# 002_motordriver_mosfet.net
KiCad netlist of a schematic drawn in EAGLE
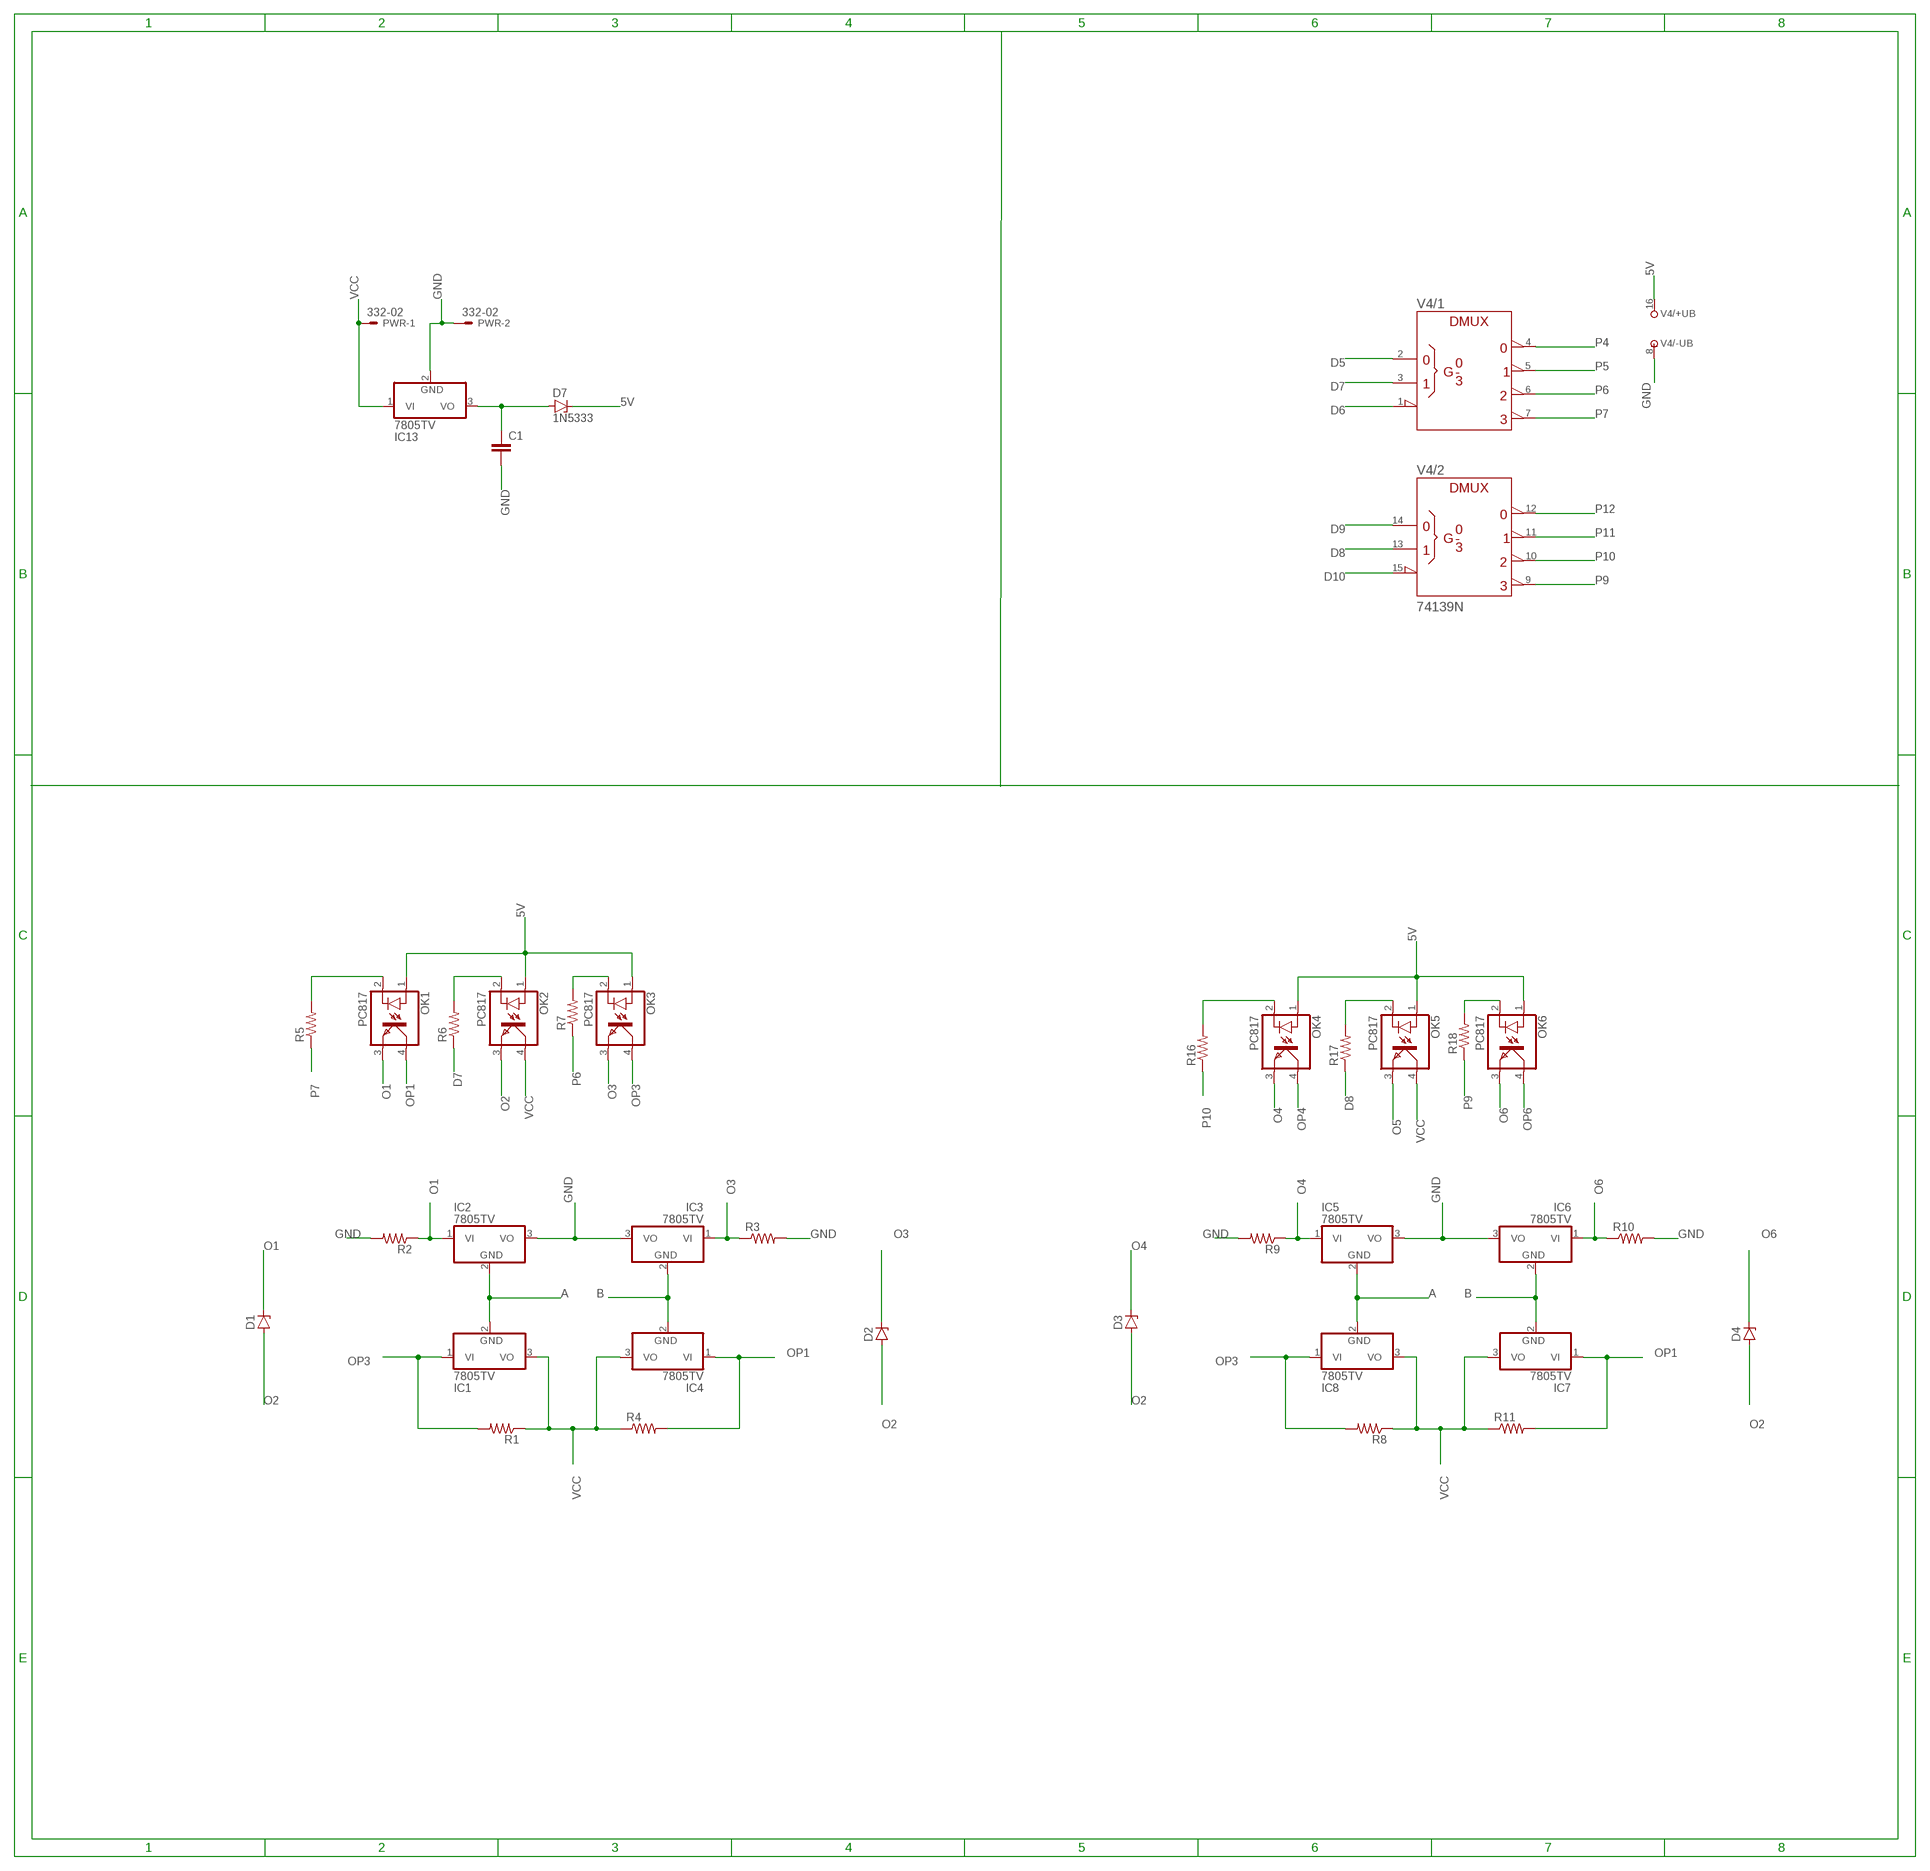
[diagram p0: schematic, sheet 1]

(export (version "E")
  (design (tool "Eeschema 10.0.6"))
  (components
    (comp (ref "C1")
      (value "C2,5-3")
      (footprint "eagle-import:C2.5-3")
      (libsource (lib "eagle-import") (part "C2,5-3"))
    )
    (comp (ref "D1")
      (value "ZENER-DIODEDO41Z10")
      (footprint "eagle-import:DO41Z10")
      (libsource (lib "eagle-import") (part "ZENER-DIODEDO41Z10"))
    )
    (comp (ref "D2")
      (value "ZENER-DIODEDO41Z10")
      (footprint "eagle-import:DO41Z10")
      (libsource (lib "eagle-import") (part "ZENER-DIODEDO41Z10"))
    )
    (comp (ref "D3")
      (value "ZENER-DIODEDO41Z10")
      (footprint "eagle-import:DO41Z10")
      (libsource (lib "eagle-import") (part "ZENER-DIODEDO41Z10"))
    )
    (comp (ref "D4")
      (value "ZENER-DIODEDO41Z10")
      (footprint "eagle-import:DO41Z10")
      (libsource (lib "eagle-import") (part "ZENER-DIODEDO41Z10"))
    )
    (comp (ref "D7")
      (value "1N5333")
      (footprint "eagle-import:C1702-15")
      (libsource (lib "eagle-import") (part "1N5333"))
    )
    (comp (ref "IC1")
      (value "7805TV")
      (footprint "eagle-import:TO220V")
      (libsource (lib "eagle-import") (part "78TV05"))
    )
    (comp (ref "IC2")
      (value "7805TV")
      (footprint "eagle-import:TO220V")
      (libsource (lib "eagle-import") (part "78TV05"))
    )
    (comp (ref "IC3")
      (value "7805TV")
      (footprint "eagle-import:TO220V")
      (libsource (lib "eagle-import") (part "78TV05"))
    )
    (comp (ref "IC4")
      (value "7805TV")
      (footprint "eagle-import:TO220V")
      (libsource (lib "eagle-import") (part "78TV05"))
    )
    (comp (ref "IC5")
      (value "7805TV")
      (footprint "eagle-import:TO220V")
      (libsource (lib "eagle-import") (part "78TV05"))
    )
    (comp (ref "IC6")
      (value "7805TV")
      (footprint "eagle-import:TO220V")
      (libsource (lib "eagle-import") (part "78TV05"))
    )
    (comp (ref "IC7")
      (value "7805TV")
      (footprint "eagle-import:TO220V")
      (libsource (lib "eagle-import") (part "78TV05"))
    )
    (comp (ref "IC8")
      (value "7805TV")
      (footprint "eagle-import:TO220V")
      (libsource (lib "eagle-import") (part "78TV05"))
    )
    (comp (ref "IC13")
      (value "7805TV")
      (footprint "eagle-import:TO220V")
      (libsource (lib "eagle-import") (part "78TV05"))
    )
    (comp (ref "OK1")
      (value "PC817")
      (footprint "eagle-import:DIL04")
      (fields (field (name "MPN") "PC817X4J000F"))
      (libsource (lib "eagle-import") (part "PC817"))
    )
    (comp (ref "OK2")
      (value "PC817")
      (footprint "eagle-import:DIL04")
      (fields (field (name "MPN") "PC817X4J000F"))
      (libsource (lib "eagle-import") (part "PC817"))
    )
    (comp (ref "OK3")
      (value "PC817")
      (footprint "eagle-import:DIL04")
      (fields (field (name "MPN") "PC817X4J000F"))
      (libsource (lib "eagle-import") (part "PC817"))
    )
    (comp (ref "OK4")
      (value "PC817")
      (footprint "eagle-import:DIL04")
      (fields (field (name "MPN") "PC817X4J000F"))
      (libsource (lib "eagle-import") (part "PC817"))
    )
    (comp (ref "OK5")
      (value "PC817")
      (footprint "eagle-import:DIL04")
      (fields (field (name "MPN") "PC817X4J000F"))
      (libsource (lib "eagle-import") (part "PC817"))
    )
    (comp (ref "OK6")
      (value "PC817")
      (footprint "eagle-import:DIL04")
      (fields (field (name "MPN") "PC817X4J000F"))
      (libsource (lib "eagle-import") (part "PC817"))
    )
    (comp (ref "PWR")
      (value "332-02")
      (footprint "eagle-import:332-02")
      (libsource (lib "eagle-import") (part "332-02"))
    )
    (comp (ref "R1")
      (value "R-US_M0805")
      (footprint "eagle-import:M0805")
      (libsource (lib "eagle-import") (part "R-US_M0805"))
    )
    (comp (ref "R2")
      (value "R-US_M0805")
      (footprint "eagle-import:M0805")
      (libsource (lib "eagle-import") (part "R-US_M0805"))
    )
    (comp (ref "R3")
      (value "R-US_M0805")
      (footprint "eagle-import:M0805")
      (libsource (lib "eagle-import") (part "R-US_M0805"))
    )
    (comp (ref "R4")
      (value "R-US_M0805")
      (footprint "eagle-import:M0805")
      (libsource (lib "eagle-import") (part "R-US_M0805"))
    )
    (comp (ref "R5")
      (value "R-US_M0805")
      (footprint "eagle-import:M0805")
      (libsource (lib "eagle-import") (part "R-US_M0805"))
    )
    (comp (ref "R6")
      (value "R-US_M0805")
      (footprint "eagle-import:M0805")
      (libsource (lib "eagle-import") (part "R-US_M0805"))
    )
    (comp (ref "R7")
      (value "R-US_M0805")
      (footprint "eagle-import:M0805")
      (libsource (lib "eagle-import") (part "R-US_M0805"))
    )
    (comp (ref "R8")
      (value "R-US_M0805")
      (footprint "eagle-import:M0805")
      (libsource (lib "eagle-import") (part "R-US_M0805"))
    )
    (comp (ref "R9")
      (value "R-US_M0805")
      (footprint "eagle-import:M0805")
      (libsource (lib "eagle-import") (part "R-US_M0805"))
    )
    (comp (ref "R10")
      (value "R-US_M0805")
      (footprint "eagle-import:M0805")
      (libsource (lib "eagle-import") (part "R-US_M0805"))
    )
    (comp (ref "R11")
      (value "R-US_M0805")
      (footprint "eagle-import:M0805")
      (libsource (lib "eagle-import") (part "R-US_M0805"))
    )
    (comp (ref "R16")
      (value "R-US_M0805")
      (footprint "eagle-import:M0805")
      (libsource (lib "eagle-import") (part "R-US_M0805"))
    )
    (comp (ref "R17")
      (value "R-US_M0805")
      (footprint "eagle-import:M0805")
      (libsource (lib "eagle-import") (part "R-US_M0805"))
    )
    (comp (ref "R18")
      (value "R-US_M0805")
      (footprint "eagle-import:M0805")
      (libsource (lib "eagle-import") (part "R-US_M0805"))
    )
    (comp (ref "V4")
      (value "74139N")
      (footprint "eagle-import:DIL16")
      (libsource (lib "eagle-import") (part "74139N"))
    )
  )
  (nets
    (net (code "1") (name "/5V") (class "Default")
      (node (ref "D7") (pin "C") (pinfunction "C_C") (pintype "passive"))
      (node (ref "OK1") (pin "1") (pinfunction "A_1") (pintype "passive"))
      (node (ref "OK2") (pin "1") (pinfunction "A_1") (pintype "passive"))
      (node (ref "OK3") (pin "1") (pinfunction "A_1") (pintype "passive"))
      (node (ref "OK4") (pin "1") (pinfunction "A_1") (pintype "passive"))
      (node (ref "OK5") (pin "1") (pinfunction "A_1") (pintype "passive"))
      (node (ref "OK6") (pin "1") (pinfunction "A_1") (pintype "passive"))
      (node (ref "V4") (pin "16") (pinfunction "+UB_16") (pintype "power_in"))
    )
    (net (code "2") (name "/A") (class "Default")
      (node (ref "IC1") (pin "2") (pinfunction "GND_2") (pintype "passive"))
      (node (ref "IC2") (pin "2") (pinfunction "GND_2") (pintype "passive"))
      (node (ref "IC5") (pin "2") (pinfunction "GND_2") (pintype "passive"))
      (node (ref "IC8") (pin "2") (pinfunction "GND_2") (pintype "passive"))
    )
    (net (code "3") (name "/B") (class "Default")
      (node (ref "IC3") (pin "2") (pinfunction "GND_2") (pintype "passive"))
      (node (ref "IC4") (pin "2") (pinfunction "GND_2") (pintype "passive"))
      (node (ref "IC6") (pin "2") (pinfunction "GND_2") (pintype "passive"))
      (node (ref "IC7") (pin "2") (pinfunction "GND_2") (pintype "passive"))
    )
    (net (code "4") (name "/D5") (class "Default")
      (node (ref "V4") (pin "2") (pinfunction "A_2") (pintype "input"))
    )
    (net (code "5") (name "/D6") (class "Default")
      (node (ref "V4") (pin "1") (pinfunction "~{G}_1") (pintype "input"))
    )
    (net (code "6") (name "/D7") (class "Default")
      (node (ref "R6") (pin "1") (pinfunction "1_1") (pintype "passive"))
      (node (ref "V4") (pin "3") (pinfunction "B_3") (pintype "input"))
    )
    (net (code "7") (name "/D8") (class "Default")
      (node (ref "R17") (pin "1") (pinfunction "1_1") (pintype "passive"))
      (node (ref "V4") (pin "13") (pinfunction "B_13") (pintype "input"))
    )
    (net (code "8") (name "/D9") (class "Default")
      (node (ref "V4") (pin "14") (pinfunction "A_14") (pintype "input"))
    )
    (net (code "9") (name "/D10") (class "Default")
      (node (ref "V4") (pin "15") (pinfunction "~{G}_15") (pintype "input"))
    )
    (net (code "10") (name "/GND") (class "Default")
      (node (ref "C1") (pin "2") (pinfunction "2_2") (pintype "passive"))
      (node (ref "IC13") (pin "2") (pinfunction "GND_2") (pintype "passive"))
      (node (ref "IC2") (pin "3") (pinfunction "VO_3") (pintype "passive"))
      (node (ref "IC3") (pin "3") (pinfunction "VO_3") (pintype "passive"))
      (node (ref "IC5") (pin "3") (pinfunction "VO_3") (pintype "passive"))
      (node (ref "IC6") (pin "3") (pinfunction "VO_3") (pintype "passive"))
      (node (ref "PWR") (pin "2") (pinfunction "S_2") (pintype "passive"))
      (node (ref "R10") (pin "2") (pinfunction "2_2") (pintype "passive"))
      (node (ref "R2") (pin "2") (pinfunction "2_2") (pintype "passive"))
      (node (ref "R3") (pin "2") (pinfunction "2_2") (pintype "passive"))
      (node (ref "R9") (pin "2") (pinfunction "2_2") (pintype "passive"))
      (node (ref "V4") (pin "8") (pinfunction "-UB_8") (pintype "power_in"))
    )
    (net (code "11") (name "/O1") (class "Default")
      (node (ref "D1") (pin "C") (pinfunction "C_C") (pintype "passive"))
      (node (ref "IC2") (pin "1") (pinfunction "VI_1") (pintype "input"))
      (node (ref "OK1") (pin "3") (pinfunction "EMIT_3") (pintype "passive"))
      (node (ref "R2") (pin "1") (pinfunction "1_1") (pintype "passive"))
    )
    (net (code "12") (name "/O2") (class "Default")
      (node (ref "D1") (pin "A") (pinfunction "A_A") (pintype "passive"))
      (node (ref "D2") (pin "A") (pinfunction "A_A") (pintype "passive"))
      (node (ref "D3") (pin "A") (pinfunction "A_A") (pintype "passive"))
      (node (ref "D4") (pin "A") (pinfunction "A_A") (pintype "passive"))
      (node (ref "OK2") (pin "3") (pinfunction "EMIT_3") (pintype "passive"))
    )
    (net (code "13") (name "/O3") (class "Default")
      (node (ref "D2") (pin "C") (pinfunction "C_C") (pintype "passive"))
      (node (ref "IC3") (pin "1") (pinfunction "VI_1") (pintype "input"))
      (node (ref "OK3") (pin "3") (pinfunction "EMIT_3") (pintype "passive"))
      (node (ref "R3") (pin "1") (pinfunction "1_1") (pintype "passive"))
    )
    (net (code "14") (name "/O4") (class "Default")
      (node (ref "D3") (pin "C") (pinfunction "C_C") (pintype "passive"))
      (node (ref "IC5") (pin "1") (pinfunction "VI_1") (pintype "input"))
      (node (ref "OK4") (pin "3") (pinfunction "EMIT_3") (pintype "passive"))
      (node (ref "R9") (pin "1") (pinfunction "1_1") (pintype "passive"))
    )
    (net (code "15") (name "/O5") (class "Default")
      (node (ref "OK5") (pin "3") (pinfunction "EMIT_3") (pintype "passive"))
    )
    (net (code "16") (name "/O6") (class "Default")
      (node (ref "D4") (pin "C") (pinfunction "C_C") (pintype "passive"))
      (node (ref "IC6") (pin "1") (pinfunction "VI_1") (pintype "input"))
      (node (ref "OK6") (pin "3") (pinfunction "EMIT_3") (pintype "passive"))
      (node (ref "R10") (pin "1") (pinfunction "1_1") (pintype "passive"))
    )
    (net (code "17") (name "/OP1") (class "Default")
      (node (ref "IC4") (pin "1") (pinfunction "VI_1") (pintype "input"))
      (node (ref "IC7") (pin "1") (pinfunction "VI_1") (pintype "input"))
      (node (ref "OK1") (pin "4") (pinfunction "COL_4") (pintype "passive"))
      (node (ref "R11") (pin "2") (pinfunction "2_2") (pintype "passive"))
      (node (ref "R4") (pin "2") (pinfunction "2_2") (pintype "passive"))
    )
    (net (code "18") (name "/OP3") (class "Default")
      (node (ref "IC1") (pin "1") (pinfunction "VI_1") (pintype "input"))
      (node (ref "IC8") (pin "1") (pinfunction "VI_1") (pintype "input"))
      (node (ref "OK3") (pin "4") (pinfunction "COL_4") (pintype "passive"))
      (node (ref "R1") (pin "2") (pinfunction "2_2") (pintype "passive"))
      (node (ref "R8") (pin "2") (pinfunction "2_2") (pintype "passive"))
    )
    (net (code "19") (name "/OP4") (class "Default")
      (node (ref "OK4") (pin "4") (pinfunction "COL_4") (pintype "passive"))
    )
    (net (code "20") (name "/OP6") (class "Default")
      (node (ref "OK6") (pin "4") (pinfunction "COL_4") (pintype "passive"))
    )
    (net (code "21") (name "/P4") (class "Default")
      (node (ref "V4") (pin "4") (pinfunction "Y0_4") (pintype "output"))
    )
    (net (code "22") (name "/P5") (class "Default")
      (node (ref "V4") (pin "5") (pinfunction "Y1_5") (pintype "output"))
    )
    (net (code "23") (name "/P6") (class "Default")
      (node (ref "R7") (pin "1") (pinfunction "1_1") (pintype "passive"))
      (node (ref "V4") (pin "6") (pinfunction "Y2_6") (pintype "output"))
    )
    (net (code "24") (name "/P7") (class "Default")
      (node (ref "R5") (pin "1") (pinfunction "1_1") (pintype "passive"))
      (node (ref "V4") (pin "7") (pinfunction "Y3_7") (pintype "output"))
    )
    (net (code "25") (name "/P9") (class "Default")
      (node (ref "R18") (pin "1") (pinfunction "1_1") (pintype "passive"))
      (node (ref "V4") (pin "9") (pinfunction "Y3_9") (pintype "output"))
    )
    (net (code "26") (name "/P10") (class "Default")
      (node (ref "R16") (pin "1") (pinfunction "1_1") (pintype "passive"))
      (node (ref "V4") (pin "10") (pinfunction "Y2_10") (pintype "output"))
    )
    (net (code "27") (name "/P11") (class "Default")
      (node (ref "V4") (pin "11") (pinfunction "Y1_11") (pintype "output"))
    )
    (net (code "28") (name "/P12") (class "Default")
      (node (ref "V4") (pin "12") (pinfunction "Y0_12") (pintype "output"))
    )
    (net (code "29") (name "/VCC") (class "Default")
      (node (ref "IC1") (pin "3") (pinfunction "VO_3") (pintype "passive"))
      (node (ref "IC13") (pin "1") (pinfunction "VI_1") (pintype "input"))
      (node (ref "IC4") (pin "3") (pinfunction "VO_3") (pintype "passive"))
      (node (ref "IC7") (pin "3") (pinfunction "VO_3") (pintype "passive"))
      (node (ref "IC8") (pin "3") (pinfunction "VO_3") (pintype "passive"))
      (node (ref "OK2") (pin "4") (pinfunction "COL_4") (pintype "passive"))
      (node (ref "OK5") (pin "4") (pinfunction "COL_4") (pintype "passive"))
      (node (ref "PWR") (pin "1") (pinfunction "S_1") (pintype "passive"))
      (node (ref "R1") (pin "1") (pinfunction "1_1") (pintype "passive"))
      (node (ref "R11") (pin "1") (pinfunction "1_1") (pintype "passive"))
      (node (ref "R4") (pin "1") (pinfunction "1_1") (pintype "passive"))
      (node (ref "R8") (pin "1") (pinfunction "1_1") (pintype "passive"))
    )
    (net (code "30") (name "Net-(IC13-VO)") (class "Default")
      (node (ref "C1") (pin "1") (pinfunction "1_1") (pintype "passive"))
      (node (ref "D7") (pin "A") (pinfunction "A_A") (pintype "passive"))
      (node (ref "IC13") (pin "3") (pinfunction "VO_3") (pintype "passive"))
    )
    (net (code "31") (name "Net-(OK1-C)") (class "Default")
      (node (ref "OK1") (pin "2") (pinfunction "C_2") (pintype "passive"))
      (node (ref "R5") (pin "2") (pinfunction "2_2") (pintype "passive"))
    )
    (net (code "32") (name "Net-(OK2-C)") (class "Default")
      (node (ref "OK2") (pin "2") (pinfunction "C_2") (pintype "passive"))
      (node (ref "R6") (pin "2") (pinfunction "2_2") (pintype "passive"))
    )
    (net (code "33") (name "Net-(OK3-C)") (class "Default")
      (node (ref "OK3") (pin "2") (pinfunction "C_2") (pintype "passive"))
      (node (ref "R7") (pin "2") (pinfunction "2_2") (pintype "passive"))
    )
    (net (code "34") (name "Net-(OK4-C)") (class "Default")
      (node (ref "OK4") (pin "2") (pinfunction "C_2") (pintype "passive"))
      (node (ref "R16") (pin "2") (pinfunction "2_2") (pintype "passive"))
    )
    (net (code "35") (name "Net-(OK5-C)") (class "Default")
      (node (ref "OK5") (pin "2") (pinfunction "C_2") (pintype "passive"))
      (node (ref "R17") (pin "2") (pinfunction "2_2") (pintype "passive"))
    )
    (net (code "36") (name "Net-(OK6-C)") (class "Default")
      (node (ref "OK6") (pin "2") (pinfunction "C_2") (pintype "passive"))
      (node (ref "R18") (pin "2") (pinfunction "2_2") (pintype "passive"))
    )
  )
)
